# SCH_BLEMouse_Keyboard_Arm_Circuit_2021-1.net
KiCad netlist of a schematic drawn in EasyEDA
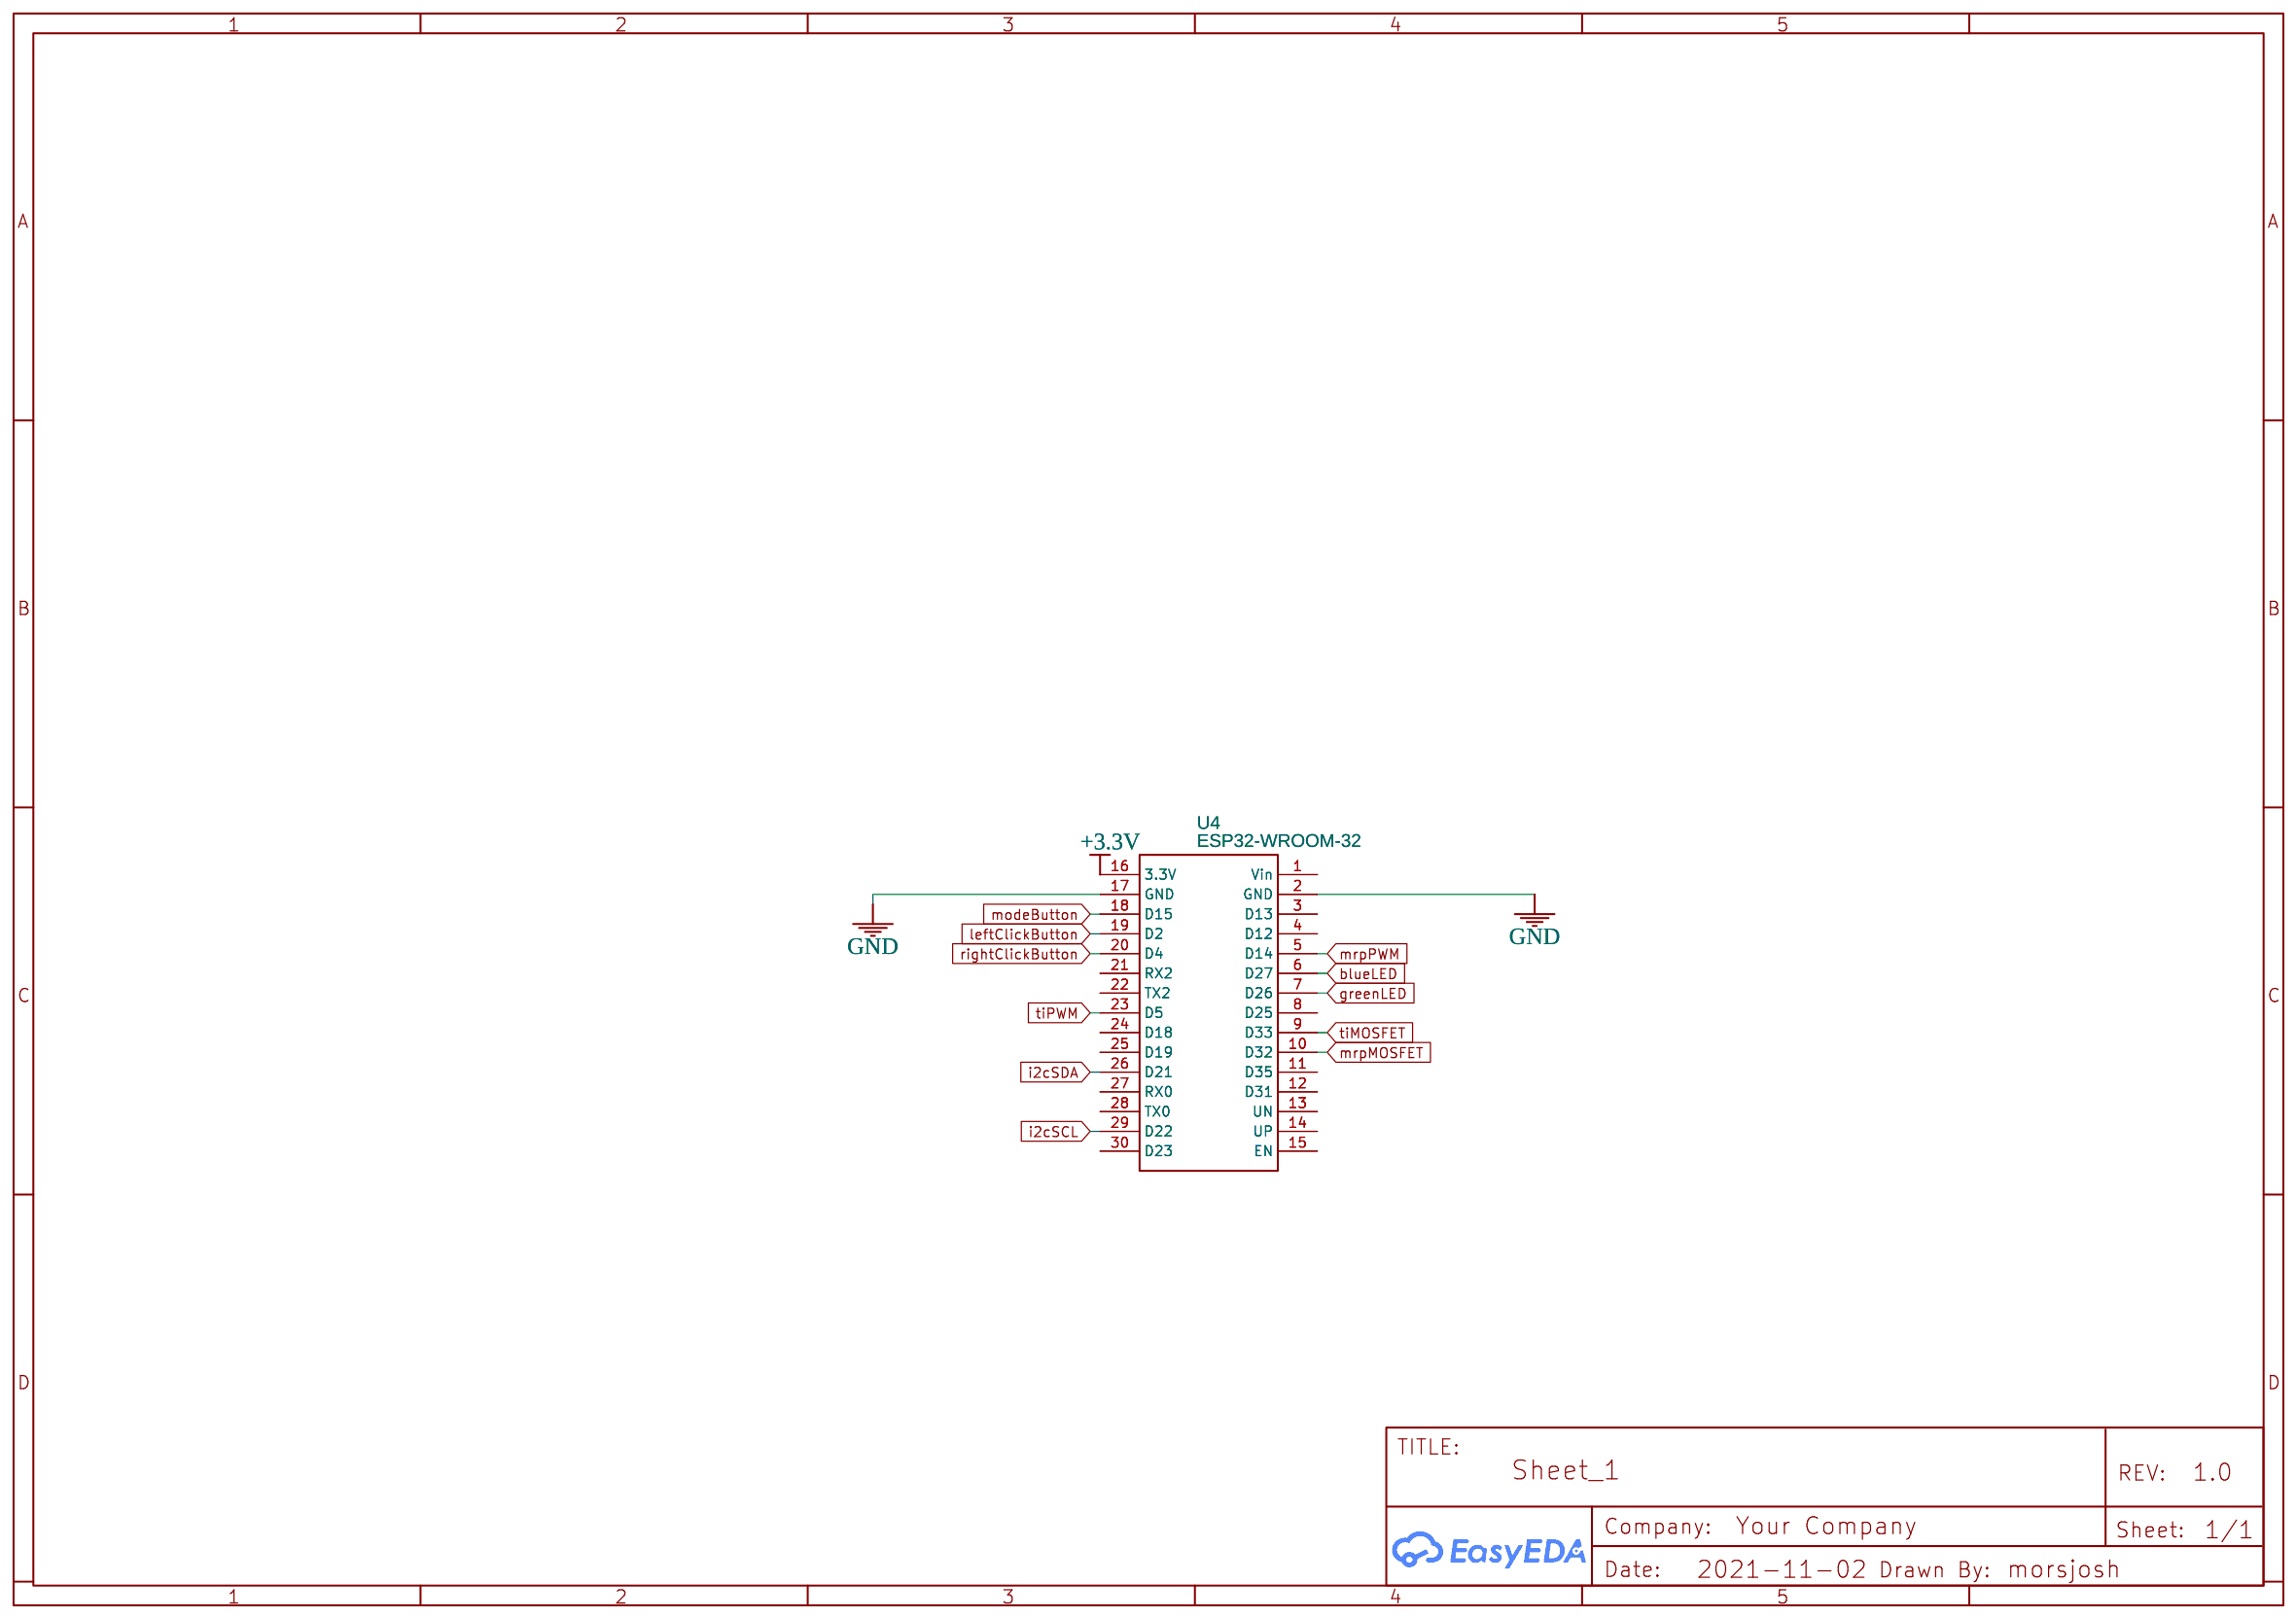
[diagram p0: ESP32_Sheet]
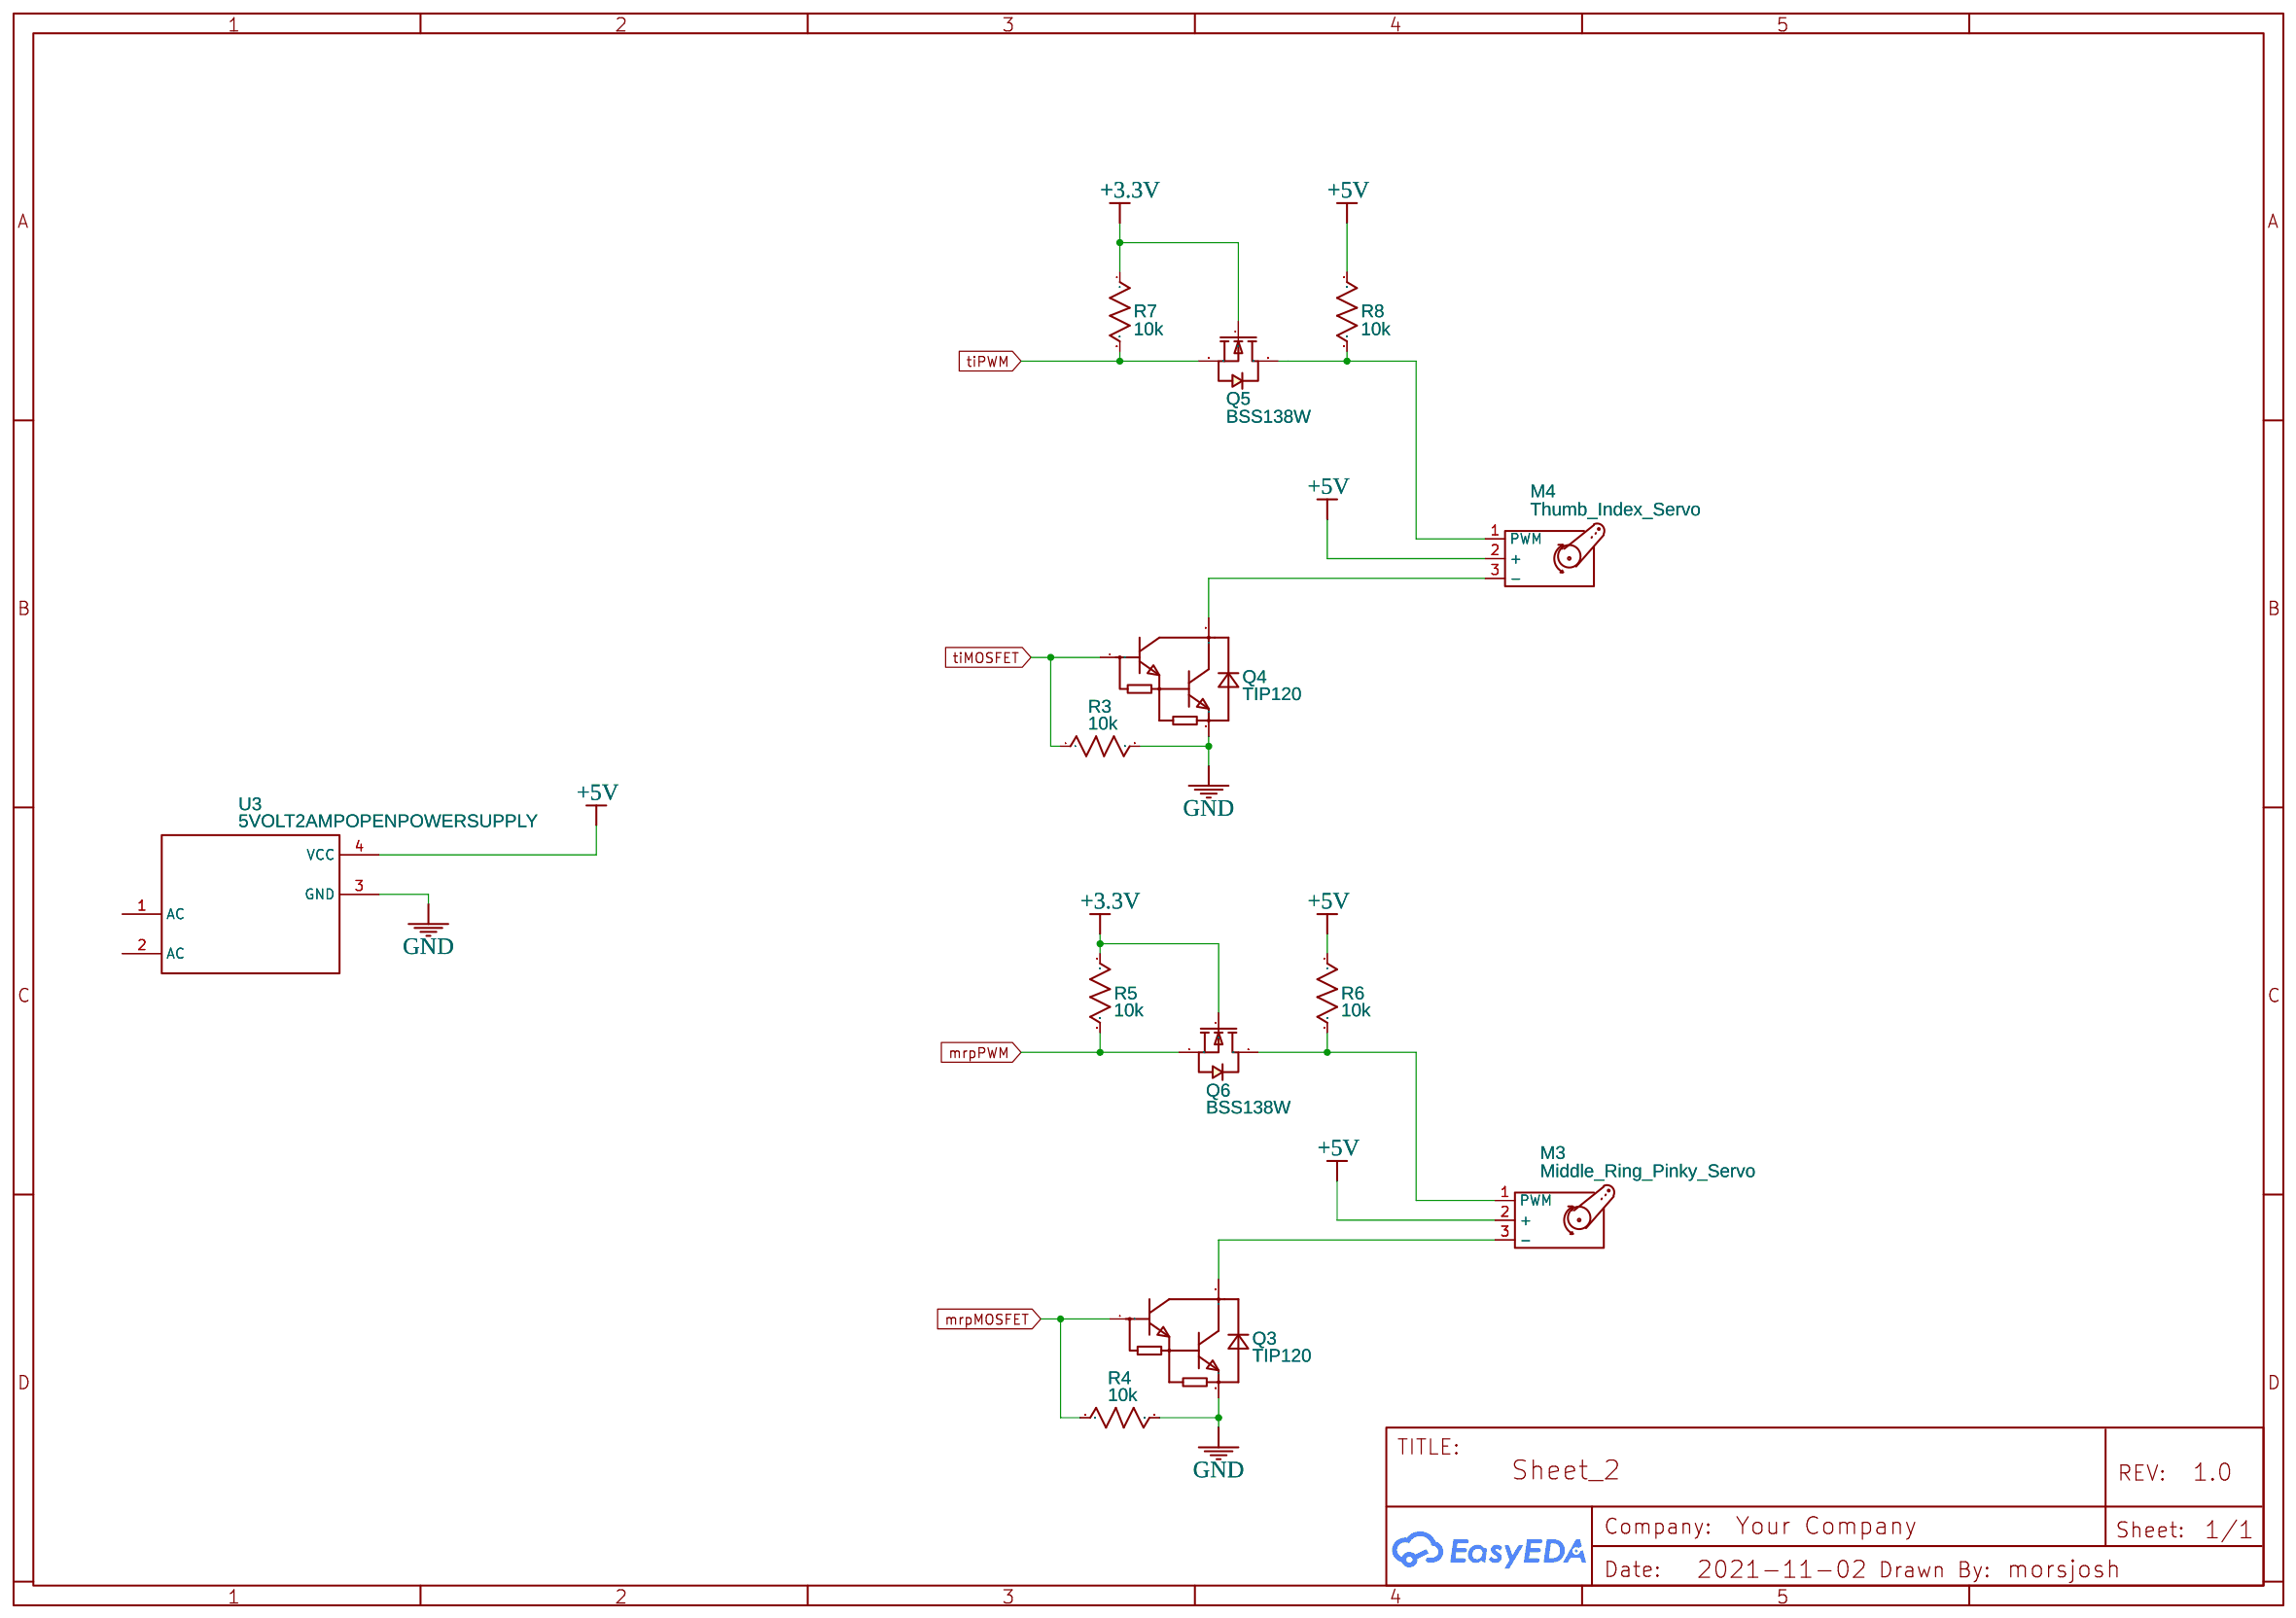
[diagram p1: Arm_Sheet]
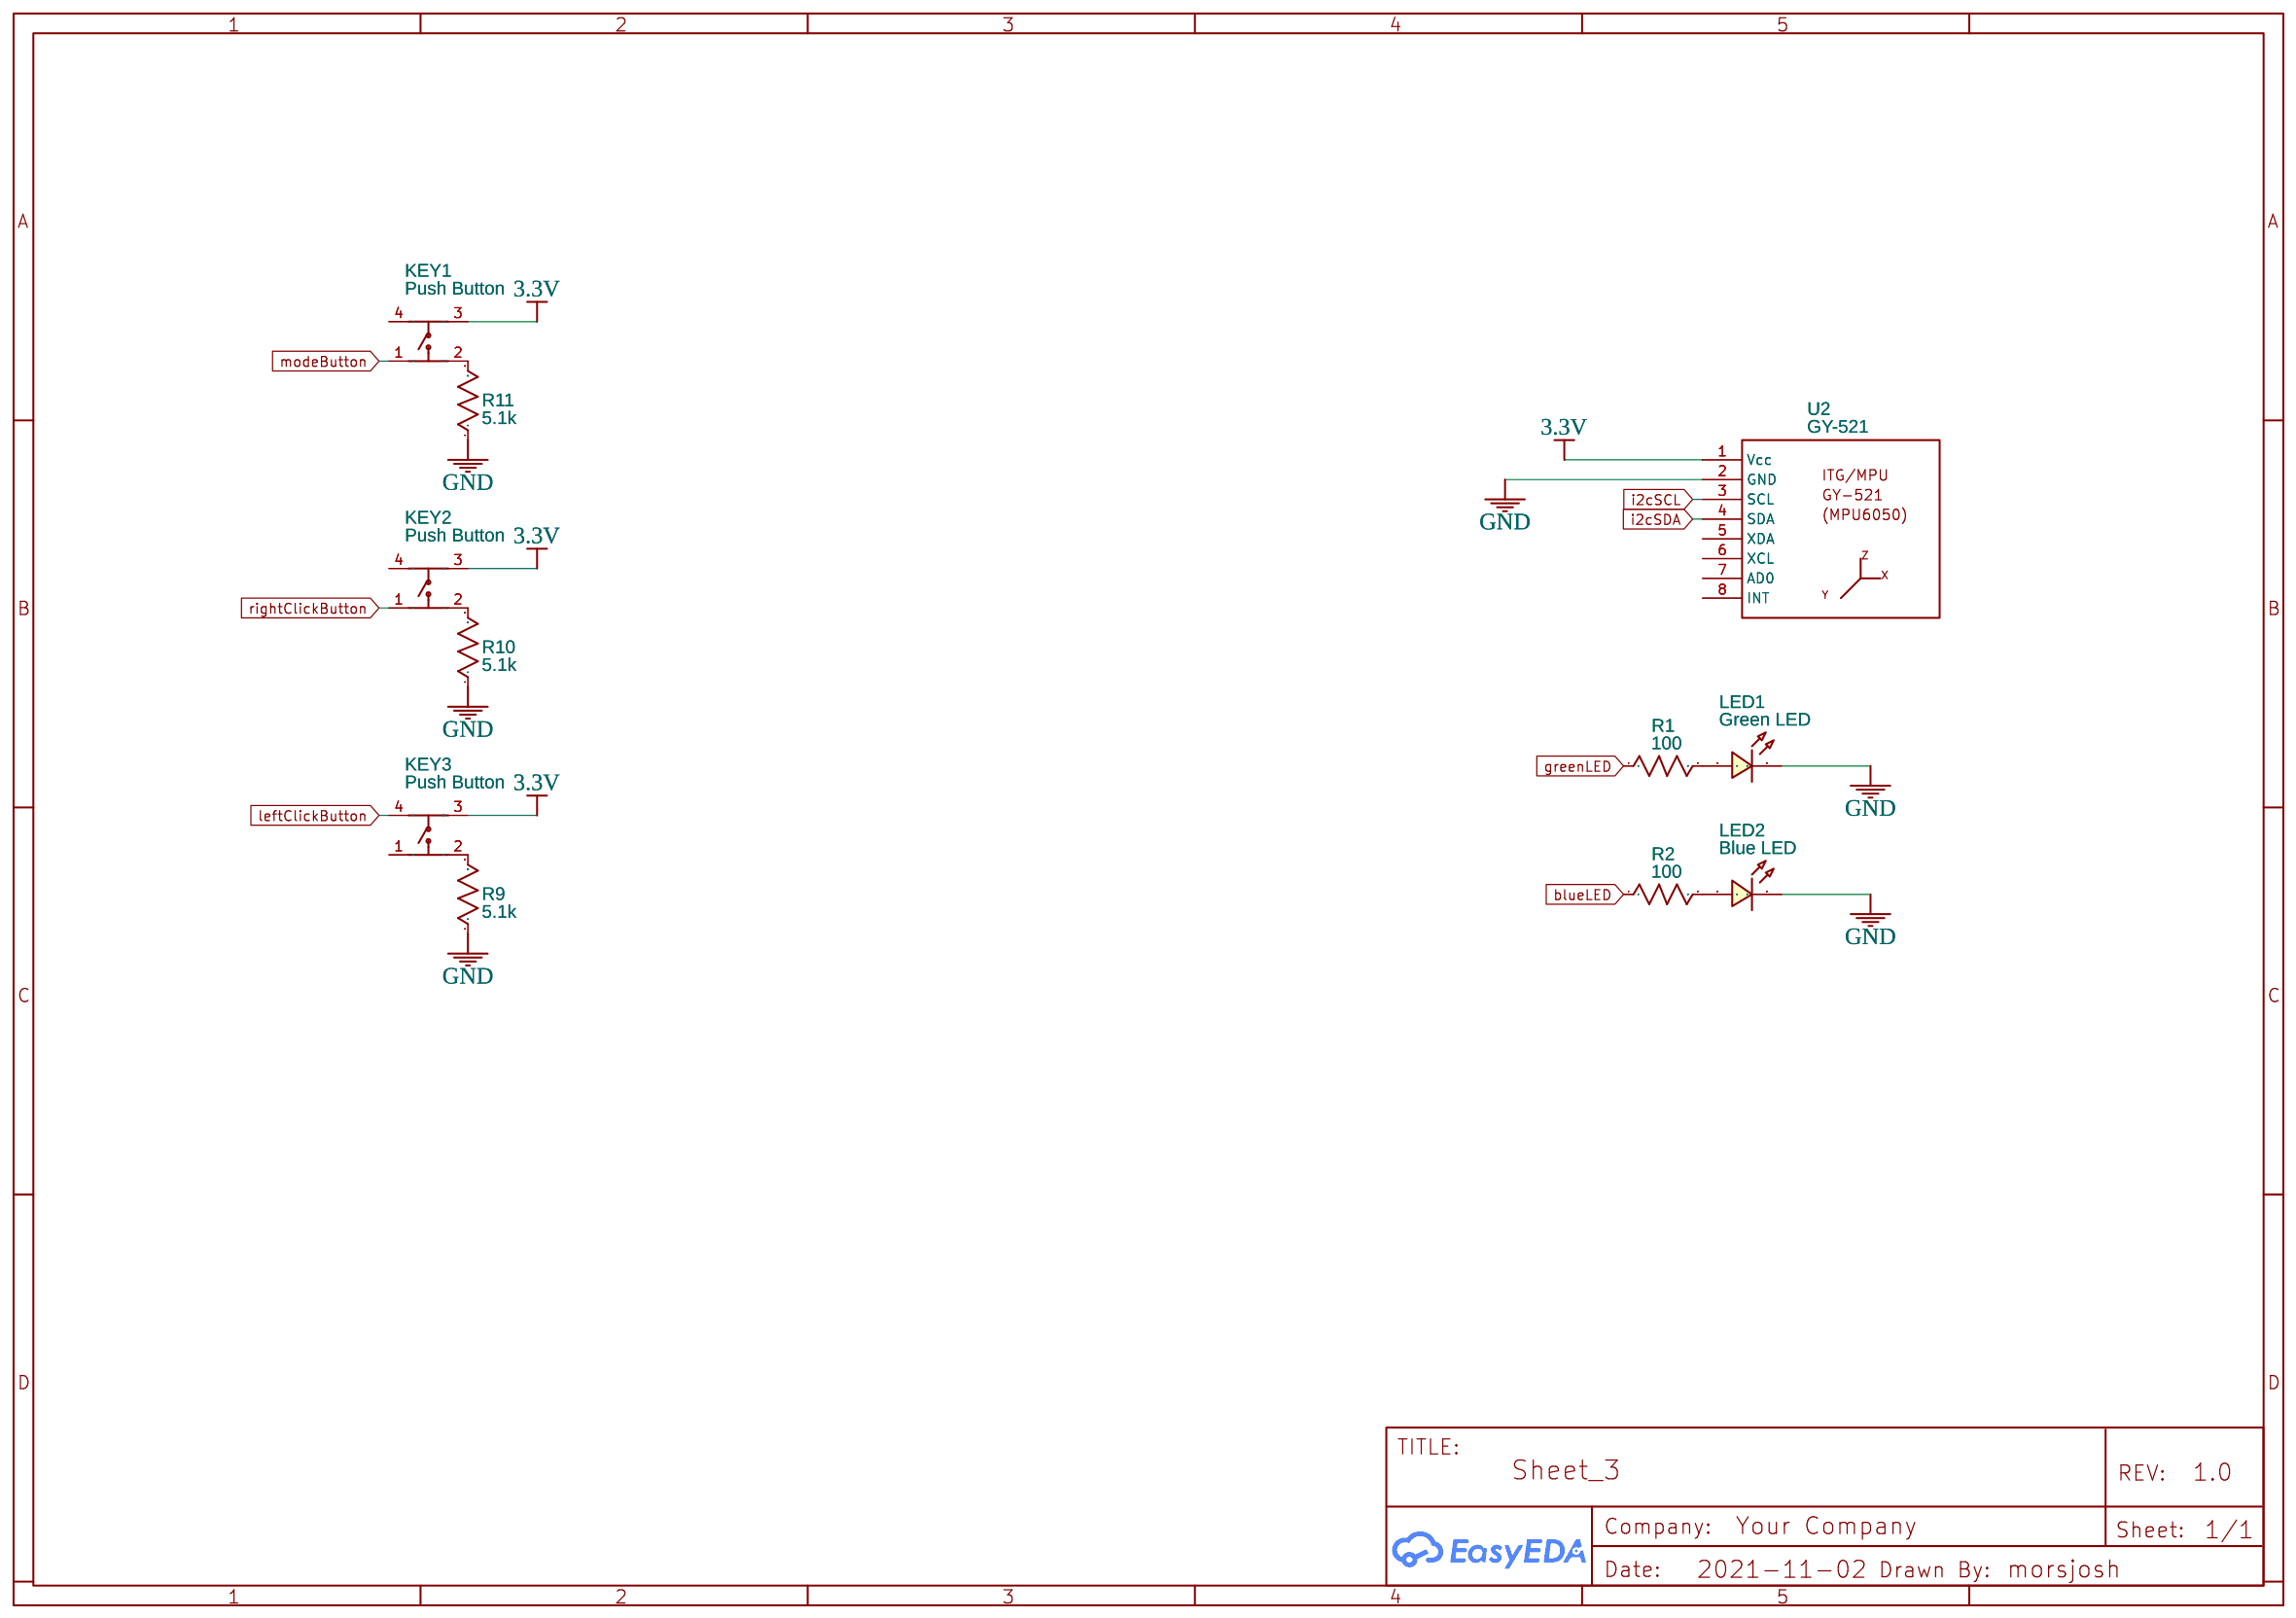
[diagram p2: BLE_Mouse/Keyboard_Sheet]

(export (version "E")
  (design (tool "Eeschema 10.0.6"))
  (components
    (comp (ref "U4") (value "ESP32-WROOM-32") (libsource (lib "") (part "ESP32-WROOM-32")))
    (comp (ref "M3") (value "Middle_Ring_Pinky_Servo") (libsource (lib "") (part "Motor_Servo")))
    (comp (ref "M4") (value "Thumb_Index_Servo") (libsource (lib "") (part "Motor_Servo")))
    (comp (ref "Q3")
      (value "TIP120")
      (fields (field (name "BOM_Supplier Part") "C262990"))
      (libsource (lib "") (part "TIP120"))
    )
    (comp (ref "Q4")
      (value "TIP120")
      (fields (field (name "BOM_Supplier Part") "C262990"))
      (libsource (lib "") (part "TIP120"))
    )
    (comp (ref "Q5")
      (value "BSS138W")
      (fields (field (name "BOM_Supplier Part") "C504052"))
      (libsource (lib "") (part "BSS138W"))
    )
    (comp (ref "Q6")
      (value "BSS138W")
      (fields (field (name "BOM_Supplier Part") "C504052"))
      (libsource (lib "") (part "BSS138W"))
    )
    (comp (ref "R3") (value "10k") (libsource (lib "") (part "R_0603_US_1")))
    (comp (ref "R4") (value "10k") (libsource (lib "") (part "R_0603_US_1")))
    (comp (ref "R5") (value "10k") (libsource (lib "") (part "R_0603_US")))
    (comp (ref "R6") (value "10k") (libsource (lib "") (part "R_0603_US")))
    (comp (ref "R7") (value "10k") (libsource (lib "") (part "R_0603_US")))
    (comp (ref "R8") (value "10k") (libsource (lib "") (part "R_0603_US")))
    (comp (ref "U3")
      (value "5VOLT2AMPOPENPOWERSUPPLY")
      (libsource (lib "") (part "5VOLT2AMPOPENPOWERSUPPLY"))
    )
    (comp (ref "KEY1")
      (value "Push Button")
      (fields
        (field (name "BOM_Manufacturer Part") "button6*6*8")
        (field (name "BOM_Supplier Part") "C59982")
      )
      (libsource (lib "") (part "button6*6*8"))
    )
    (comp (ref "KEY2")
      (value "Push Button")
      (fields
        (field (name "BOM_Manufacturer Part") "button6*6*8")
        (field (name "BOM_Supplier Part") "C59982")
      )
      (libsource (lib "") (part "button6*6*8"))
    )
    (comp (ref "KEY3")
      (value "Push Button")
      (fields
        (field (name "BOM_Manufacturer Part") "button6*6*8")
        (field (name "BOM_Supplier Part") "C59982")
      )
      (libsource (lib "") (part "button6*6*8"))
    )
    (comp (ref "LED1")
      (value "Green LED")
      (fields
        (field (name "BOM_Manufacturer Part") "19-217/R6C-AL1M2VY/3T")
        (field (name "BOM_Supplier Part") "C72044")
      )
      (libsource (lib "") (part "LED-0603_R"))
    )
    (comp (ref "LED2")
      (value "Blue LED")
      (fields
        (field (name "BOM_Manufacturer Part") "19-217/R6C-AL1M2VY/3T")
        (field (name "BOM_Supplier Part") "C72044")
      )
      (libsource (lib "") (part "LED-0603_R"))
    )
    (comp (ref "R1") (value "100") (libsource (lib "") (part "R_0201_US_1")))
    (comp (ref "R2") (value "100") (libsource (lib "") (part "R_0201_US_1")))
    (comp (ref "R9") (value "5.1k") (libsource (lib "") (part "R_0201_US")))
    (comp (ref "R10") (value "5.1k") (libsource (lib "") (part "R_0201_US")))
    (comp (ref "R11") (value "5.1k") (libsource (lib "") (part "R_0201_US")))
    (comp (ref "U2") (value "GY-521") (libsource (lib "") (part "GY-521")))
  )
  (nets
    (net (code "1") (name "+3.3V") (class "Default")
      (node (ref "Q5") (pin "1") (pinfunction "G_1") (pintype "unspecified"))
      (node (ref "Q6") (pin "1") (pinfunction "G_1") (pintype "unspecified"))
      (node (ref "R5") (pin "1") (pinfunction "1_1") (pintype "unspecified"))
      (node (ref "R7") (pin "1") (pinfunction "1_1") (pintype "unspecified"))
      (node (ref "U4") (pin "16") (pinfunction "3.3V_16") (pintype "unspecified"))
    )
    (net (code "2") (name "+5V") (class "Default")
      (node (ref "M3") (pin "2") (pinfunction "+_2") (pintype "unspecified"))
      (node (ref "M4") (pin "2") (pinfunction "+_2") (pintype "unspecified"))
      (node (ref "R6") (pin "1") (pinfunction "1_1") (pintype "unspecified"))
      (node (ref "R8") (pin "1") (pinfunction "1_1") (pintype "unspecified"))
      (node (ref "U3") (pin "4") (pinfunction "VCC_4") (pintype "unspecified"))
    )
    (net (code "3") (name "3.3V") (class "Default")
      (node (ref "KEY1") (pin "3") (pinfunction "3_3") (pintype "unspecified"))
      (node (ref "KEY2") (pin "3") (pinfunction "3_3") (pintype "unspecified"))
      (node (ref "KEY3") (pin "3") (pinfunction "3_3") (pintype "unspecified"))
      (node (ref "U2") (pin "1") (pinfunction "Vcc_1") (pintype "unspecified"))
    )
    (net (code "4") (name "GND") (class "Default")
      (node (ref "LED1") (pin "2") (pinfunction "2_2") (pintype "unspecified"))
      (node (ref "LED2") (pin "2") (pinfunction "2_2") (pintype "unspecified"))
      (node (ref "Q3") (pin "3") (pinfunction "E_3") (pintype "input"))
      (node (ref "Q4") (pin "3") (pinfunction "E_3") (pintype "input"))
      (node (ref "R10") (pin "1") (pinfunction "1_1") (pintype "unspecified"))
      (node (ref "R11") (pin "1") (pinfunction "1_1") (pintype "unspecified"))
      (node (ref "R3") (pin "2") (pinfunction "2_2") (pintype "unspecified"))
      (node (ref "R4") (pin "2") (pinfunction "2_2") (pintype "unspecified"))
      (node (ref "R9") (pin "1") (pinfunction "1_1") (pintype "unspecified"))
      (node (ref "U2") (pin "2") (pinfunction "GND_2") (pintype "unspecified"))
      (node (ref "U3") (pin "3") (pinfunction "GND_3") (pintype "unspecified"))
      (node (ref "U4") (pin "17") (pinfunction "GND_17") (pintype "unspecified"))
      (node (ref "U4") (pin "2") (pinfunction "GND_2") (pintype "unspecified"))
    )
    (net (code "5") (name "Net-(KEY1-Pad2)") (class "Default")
      (node (ref "KEY1") (pin "2") (pinfunction "2_2") (pintype "unspecified"))
      (node (ref "R11") (pin "2") (pinfunction "2_2") (pintype "unspecified"))
    )
    (net (code "6") (name "Net-(KEY2-Pad2)") (class "Default")
      (node (ref "KEY2") (pin "2") (pinfunction "2_2") (pintype "unspecified"))
      (node (ref "R10") (pin "2") (pinfunction "2_2") (pintype "unspecified"))
    )
    (net (code "7") (name "Net-(KEY3-Pad2)") (class "Default")
      (node (ref "KEY3") (pin "2") (pinfunction "2_2") (pintype "unspecified"))
      (node (ref "R9") (pin "2") (pinfunction "2_2") (pintype "unspecified"))
    )
    (net (code "8") (name "Net-(LED1-Pad1)") (class "Default")
      (node (ref "LED1") (pin "1") (pinfunction "1_1") (pintype "unspecified"))
      (node (ref "R1") (pin "2") (pinfunction "2_2") (pintype "unspecified"))
    )
    (net (code "9") (name "Net-(LED2-Pad1)") (class "Default")
      (node (ref "LED2") (pin "1") (pinfunction "1_1") (pintype "unspecified"))
      (node (ref "R2") (pin "2") (pinfunction "2_2") (pintype "unspecified"))
    )
    (net (code "10") (name "Net-(M3--)") (class "Default")
      (node (ref "M3") (pin "3") (pinfunction "-_3") (pintype "unspecified"))
      (node (ref "Q3") (pin "2") (pinfunction "C_2") (pintype "input"))
    )
    (net (code "11") (name "Net-(M3-PWM)") (class "Default")
      (node (ref "M3") (pin "1") (pinfunction "PWM_1") (pintype "unspecified"))
      (node (ref "Q6") (pin "3") (pinfunction "D_3") (pintype "unspecified"))
      (node (ref "R6") (pin "2") (pinfunction "2_2") (pintype "unspecified"))
    )
    (net (code "12") (name "Net-(M4--)") (class "Default")
      (node (ref "M4") (pin "3") (pinfunction "-_3") (pintype "unspecified"))
      (node (ref "Q4") (pin "2") (pinfunction "C_2") (pintype "input"))
    )
    (net (code "13") (name "Net-(M4-PWM)") (class "Default")
      (node (ref "M4") (pin "1") (pinfunction "PWM_1") (pintype "unspecified"))
      (node (ref "Q5") (pin "3") (pinfunction "D_3") (pintype "unspecified"))
      (node (ref "R8") (pin "2") (pinfunction "2_2") (pintype "unspecified"))
    )
    (net (code "14") (name "blueLED") (class "Default")
      (node (ref "R2") (pin "1") (pinfunction "1_1") (pintype "unspecified"))
      (node (ref "U4") (pin "6") (pinfunction "D27_6") (pintype "unspecified"))
    )
    (net (code "15") (name "greenLED") (class "Default")
      (node (ref "R1") (pin "1") (pinfunction "1_1") (pintype "unspecified"))
      (node (ref "U4") (pin "7") (pinfunction "D26_7") (pintype "unspecified"))
    )
    (net (code "16") (name "i2cSCL") (class "Default")
      (node (ref "U2") (pin "3") (pinfunction "SCL_3") (pintype "unspecified"))
      (node (ref "U4") (pin "29") (pinfunction "D22_29") (pintype "unspecified"))
    )
    (net (code "17") (name "i2cSDA") (class "Default")
      (node (ref "U2") (pin "4") (pinfunction "SDA_4") (pintype "unspecified"))
      (node (ref "U4") (pin "26") (pinfunction "D21_26") (pintype "unspecified"))
    )
    (net (code "18") (name "leftClickButton") (class "Default")
      (node (ref "KEY3") (pin "4") (pinfunction "4_4") (pintype "unspecified"))
      (node (ref "U4") (pin "19") (pinfunction "D2_19") (pintype "unspecified"))
    )
    (net (code "19") (name "modeButton") (class "Default")
      (node (ref "KEY1") (pin "1") (pinfunction "1_1") (pintype "unspecified"))
      (node (ref "U4") (pin "18") (pinfunction "D15_18") (pintype "unspecified"))
    )
    (net (code "20") (name "mrpMOSFET") (class "Default")
      (node (ref "Q3") (pin "1") (pinfunction "B_1") (pintype "input"))
      (node (ref "R4") (pin "1") (pinfunction "1_1") (pintype "unspecified"))
      (node (ref "U4") (pin "10") (pinfunction "D32_10") (pintype "unspecified"))
    )
    (net (code "21") (name "mrpPWM") (class "Default")
      (node (ref "Q6") (pin "2") (pinfunction "S_2") (pintype "unspecified"))
      (node (ref "R5") (pin "2") (pinfunction "2_2") (pintype "unspecified"))
      (node (ref "U4") (pin "5") (pinfunction "D14_5") (pintype "unspecified"))
    )
    (net (code "22") (name "rightClickButton") (class "Default")
      (node (ref "KEY2") (pin "1") (pinfunction "1_1") (pintype "unspecified"))
      (node (ref "U4") (pin "20") (pinfunction "D4_20") (pintype "unspecified"))
    )
    (net (code "23") (name "tiMOSFET") (class "Default")
      (node (ref "Q4") (pin "1") (pinfunction "B_1") (pintype "input"))
      (node (ref "R3") (pin "1") (pinfunction "1_1") (pintype "unspecified"))
      (node (ref "U4") (pin "9") (pinfunction "D33_9") (pintype "unspecified"))
    )
    (net (code "24") (name "tiPWM") (class "Default")
      (node (ref "Q5") (pin "2") (pinfunction "S_2") (pintype "unspecified"))
      (node (ref "R7") (pin "2") (pinfunction "2_2") (pintype "unspecified"))
      (node (ref "U4") (pin "23") (pinfunction "D5_23") (pintype "unspecified"))
    )
    (net (code "25") (name "unconnected-(KEY1-Pad4)") (class "Default")
      (node (ref "KEY1") (pin "4") (pinfunction "4_4") (pintype "unspecified"))
    )
    (net (code "26") (name "unconnected-(KEY2-Pad4)") (class "Default")
      (node (ref "KEY2") (pin "4") (pinfunction "4_4") (pintype "unspecified"))
    )
    (net (code "27") (name "unconnected-(KEY3-Pad1)") (class "Default")
      (node (ref "KEY3") (pin "1") (pinfunction "1_1") (pintype "unspecified"))
    )
    (net (code "28") (name "unconnected-(U2-AD0-Pad7)") (class "Default")
      (node (ref "U2") (pin "7") (pinfunction "AD0_7") (pintype "unspecified"))
    )
    (net (code "29") (name "unconnected-(U2-INT-Pad8)") (class "Default")
      (node (ref "U2") (pin "8") (pinfunction "INT_8") (pintype "unspecified"))
    )
    (net (code "30") (name "unconnected-(U2-XCL-Pad6)") (class "Default")
      (node (ref "U2") (pin "6") (pinfunction "XCL_6") (pintype "unspecified"))
    )
    (net (code "31") (name "unconnected-(U2-XDA-Pad5)") (class "Default")
      (node (ref "U2") (pin "5") (pinfunction "XDA_5") (pintype "unspecified"))
    )
    (net (code "32") (name "unconnected-(U3-AC-Pad1)") (class "Default")
      (node (ref "U3") (pin "1") (pinfunction "AC_1") (pintype "unspecified"))
    )
    (net (code "33") (name "unconnected-(U3-AC-Pad2)") (class "Default")
      (node (ref "U3") (pin "2") (pinfunction "AC_2") (pintype "unspecified"))
    )
    (net (code "34") (name "unconnected-(U4-D12-Pad4)") (class "Default")
      (node (ref "U4") (pin "4") (pinfunction "D12_4") (pintype "unspecified"))
    )
    (net (code "35") (name "unconnected-(U4-D13-Pad3)") (class "Default")
      (node (ref "U4") (pin "3") (pinfunction "D13_3") (pintype "unspecified"))
    )
    (net (code "36") (name "unconnected-(U4-D18-Pad24)") (class "Default")
      (node (ref "U4") (pin "24") (pinfunction "D18_24") (pintype "unspecified"))
    )
    (net (code "37") (name "unconnected-(U4-D19-Pad25)") (class "Default")
      (node (ref "U4") (pin "25") (pinfunction "D19_25") (pintype "unspecified"))
    )
    (net (code "38") (name "unconnected-(U4-D23-Pad30)") (class "Default")
      (node (ref "U4") (pin "30") (pinfunction "D23_30") (pintype "unspecified"))
    )
    (net (code "39") (name "unconnected-(U4-D25-Pad8)") (class "Default")
      (node (ref "U4") (pin "8") (pinfunction "D25_8") (pintype "unspecified"))
    )
    (net (code "40") (name "unconnected-(U4-D31-Pad12)") (class "Default")
      (node (ref "U4") (pin "12") (pinfunction "D31_12") (pintype "unspecified"))
    )
    (net (code "41") (name "unconnected-(U4-D35-Pad11)") (class "Default")
      (node (ref "U4") (pin "11") (pinfunction "D35_11") (pintype "unspecified"))
    )
    (net (code "42") (name "unconnected-(U4-EN-Pad15)") (class "Default")
      (node (ref "U4") (pin "15") (pinfunction "EN_15") (pintype "unspecified"))
    )
    (net (code "43") (name "unconnected-(U4-RX0-Pad27)") (class "Default")
      (node (ref "U4") (pin "27") (pinfunction "RX0_27") (pintype "unspecified"))
    )
    (net (code "44") (name "unconnected-(U4-RX2-Pad21)") (class "Default")
      (node (ref "U4") (pin "21") (pinfunction "RX2_21") (pintype "unspecified"))
    )
    (net (code "45") (name "unconnected-(U4-TX0-Pad28)") (class "Default")
      (node (ref "U4") (pin "28") (pinfunction "TX0_28") (pintype "unspecified"))
    )
    (net (code "46") (name "unconnected-(U4-TX2-Pad22)") (class "Default")
      (node (ref "U4") (pin "22") (pinfunction "TX2_22") (pintype "unspecified"))
    )
    (net (code "47") (name "unconnected-(U4-UN-Pad13)") (class "Default")
      (node (ref "U4") (pin "13") (pinfunction "UN_13") (pintype "unspecified"))
    )
    (net (code "48") (name "unconnected-(U4-UP-Pad14)") (class "Default")
      (node (ref "U4") (pin "14") (pinfunction "UP_14") (pintype "unspecified"))
    )
    (net (code "49") (name "unconnected-(U4-Vin-Pad1)") (class "Default")
      (node (ref "U4") (pin "1") (pinfunction "Vin_1") (pintype "unspecified"))
    )
  )
)
